# Frozen_Slimes_v2_BMI.net
KiCad netlist of a schematic drawn in EasyEDA
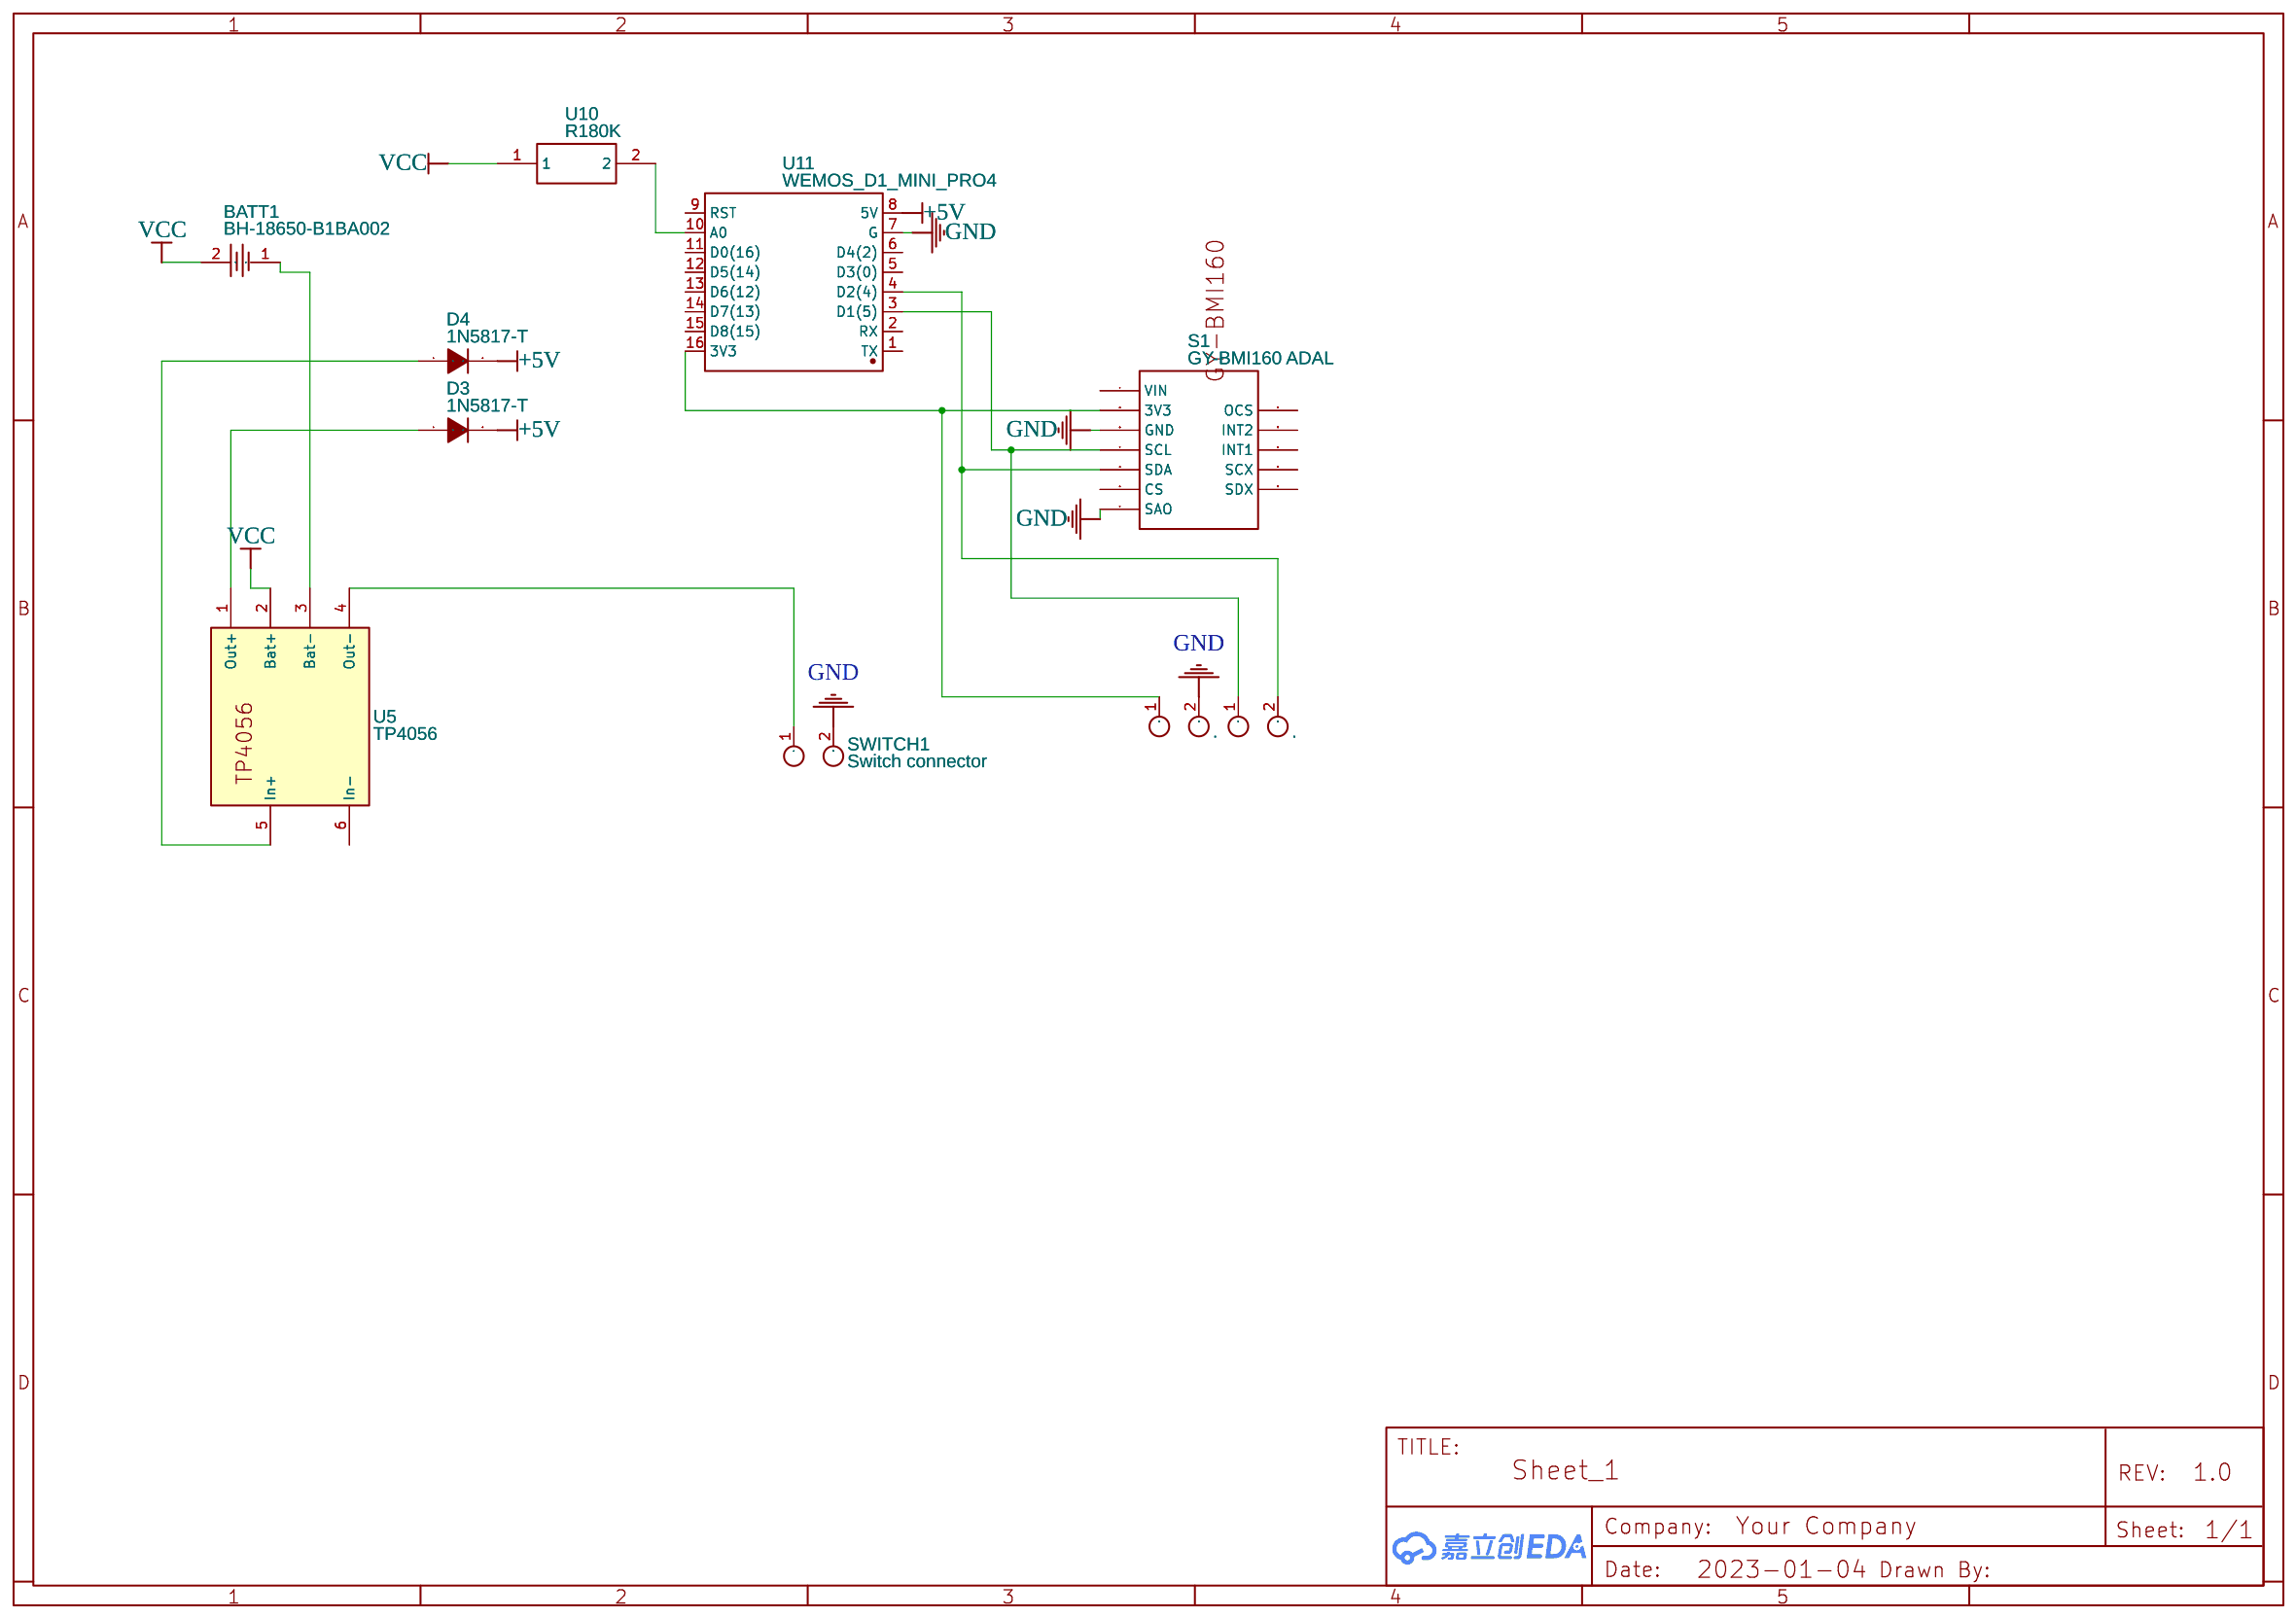
[diagram p0: schematic sheet]

(export (version "E")
  (design (tool "Eeschema 10.0.6"))
  (components
    (comp (ref "BATT1")
      (value "BH-18650-B1BA002")
      (fields (field (name "BOM_Supplier Part") "C2988620"))
      (libsource (lib "") (part "BH-18650-B1BA002"))
    )
    (comp (ref "D3")
      (value "1N5817-T")
      (fields (field (name "BOM_Supplier Part") "C507852"))
      (libsource (lib "") (part "1N5817-T"))
    )
    (comp (ref "D4")
      (value "1N5817-T")
      (fields (field (name "BOM_Supplier Part") "C507852"))
      (libsource (lib "") (part "1N5817-T"))
    )
    (comp (ref "S1") (value "GY-BMI160 ADAL") (libsource (lib "") (part "GY-BMI160 ADAL")))
    (comp (ref "SWITCH1") (value "Switch connector") (libsource (lib "") (part "2XSOLDER PAD")))
    (comp (ref "U5") (value "TP4056") (libsource (lib "") (part "TP4056")))
    (comp (ref "U8") (value ".") (libsource (lib "") (part "2XSOLDER PAD_1")))
    (comp (ref "U9") (value ".") (libsource (lib "") (part "2XSOLDER PAD_1")))
    (comp (ref "U10") (value "R180K") (libsource (lib "") (part "R180K")))
    (comp (ref "U11")
      (value "WEMOS_D1_MINI_PRO4")
      (fields
        (field (name "BOM_Manufacturer Part") "Wemos_D1_mini_Pro4")
        (field (name "BOM_Supplier Part") "C2837266")
      )
      (libsource (lib "") (part "WEMOS_D1_MINI_PRO4"))
    )
  )
  (nets
    (net (code "1") (name "+5V") (class "Default")
      (node (ref "D3") (pin "2") (pinfunction "K_2") (pintype "unspecified"))
      (node (ref "D4") (pin "2") (pinfunction "K_2") (pintype "unspecified"))
      (node (ref "U11") (pin "8") (pinfunction "5V_8") (pintype "unspecified"))
    )
    (net (code "2") (name "GND") (class "Default")
      (node (ref "S1") (pin "1") (pinfunction "SAO_1") (pintype "unspecified"))
      (node (ref "S1") (pin "5") (pinfunction "GND_5") (pintype "unspecified"))
      (node (ref "SWITCH1") (pin "2") (pinfunction "2_2") (pintype "unspecified"))
      (node (ref "U11") (pin "7") (pinfunction "G_7") (pintype "unspecified"))
      (node (ref "U9") (pin "2") (pinfunction "2_2") (pintype "unspecified"))
    )
    (net (code "3") (name "Net-(D3-A)") (class "Default")
      (node (ref "D3") (pin "1") (pinfunction "A_1") (pintype "unspecified"))
      (node (ref "U5") (pin "1") (pinfunction "Out+_1") (pintype "unspecified"))
    )
    (net (code "4") (name "Net-(D4-A)") (class "Default")
      (node (ref "D4") (pin "1") (pinfunction "A_1") (pintype "unspecified"))
      (node (ref "U5") (pin "5") (pinfunction "In+_5") (pintype "unspecified"))
    )
    (net (code "5") (name "Net-(S1-3V3)") (class "Default")
      (node (ref "S1") (pin "6") (pinfunction "3V3_6") (pintype "unspecified"))
      (node (ref "U11") (pin "16") (pinfunction "3V3_16") (pintype "unspecified"))
      (node (ref "U9") (pin "1") (pinfunction "1_1") (pintype "unspecified"))
    )
    (net (code "6") (name "Net-(S1-SCL)") (class "Default")
      (node (ref "S1") (pin "4") (pinfunction "SCL_4") (pintype "unspecified"))
      (node (ref "U11") (pin "3") (pinfunction "D1(5)_3") (pintype "unspecified"))
      (node (ref "U8") (pin "1") (pinfunction "1_1") (pintype "unspecified"))
    )
    (net (code "7") (name "Net-(S1-SDA)") (class "Default")
      (node (ref "S1") (pin "3") (pinfunction "SDA_3") (pintype "unspecified"))
      (node (ref "U11") (pin "4") (pinfunction "D2(4)_4") (pintype "unspecified"))
      (node (ref "U8") (pin "2") (pinfunction "2_2") (pintype "unspecified"))
    )
    (net (code "8") (name "Net-(U5-Bat-)") (class "Default")
      (node (ref "BATT1") (pin "1") (pinfunction "1_1") (pintype "input"))
      (node (ref "U5") (pin "3") (pinfunction "Bat-_3") (pintype "unspecified"))
    )
    (net (code "9") (name "Net-(U5-Out-)") (class "Default")
      (node (ref "SWITCH1") (pin "1") (pinfunction "1_1") (pintype "unspecified"))
      (node (ref "U5") (pin "4") (pinfunction "Out-_4") (pintype "unspecified"))
    )
    (net (code "10") (name "Net-(U11-A0)") (class "Default")
      (node (ref "U10") (pin "2") (pinfunction "2_2") (pintype "unspecified"))
      (node (ref "U11") (pin "10") (pinfunction "A0_10") (pintype "unspecified"))
    )
    (net (code "11") (name "VCC") (class "Default")
      (node (ref "BATT1") (pin "2") (pinfunction "2_2") (pintype "input"))
      (node (ref "U10") (pin "1") (pinfunction "1_1") (pintype "unspecified"))
      (node (ref "U5") (pin "2") (pinfunction "Bat+_2") (pintype "unspecified"))
    )
    (net (code "12") (name "unconnected-(S1-CS-Pad2)") (class "Default")
      (node (ref "S1") (pin "2") (pinfunction "CS_2") (pintype "unspecified"))
    )
    (net (code "13") (name "unconnected-(S1-INT1-Pad10)") (class "Default")
      (node (ref "S1") (pin "10") (pinfunction "INT1_10") (pintype "unspecified"))
    )
    (net (code "14") (name "unconnected-(S1-INT2-Pad9)") (class "Default")
      (node (ref "S1") (pin "9") (pinfunction "INT2_9") (pintype "unspecified"))
    )
    (net (code "15") (name "unconnected-(S1-OCS-Pad8)") (class "Default")
      (node (ref "S1") (pin "8") (pinfunction "OCS_8") (pintype "unspecified"))
    )
    (net (code "16") (name "unconnected-(S1-SCX-Pad11)") (class "Default")
      (node (ref "S1") (pin "11") (pinfunction "SCX_11") (pintype "unspecified"))
    )
    (net (code "17") (name "unconnected-(S1-SDX-Pad12)") (class "Default")
      (node (ref "S1") (pin "12") (pinfunction "SDX_12") (pintype "unspecified"))
    )
    (net (code "18") (name "unconnected-(S1-VIN-Pad7)") (class "Default")
      (node (ref "S1") (pin "7") (pinfunction "VIN_7") (pintype "unspecified"))
    )
    (net (code "19") (name "unconnected-(U5-In--Pad6)") (class "Default")
      (node (ref "U5") (pin "6") (pinfunction "In-_6") (pintype "unspecified"))
    )
    (net (code "20") (name "unconnected-(U11-D0(16)-Pad11)") (class "Default")
      (node (ref "U11") (pin "11") (pinfunction "D0(16)_11") (pintype "unspecified"))
    )
    (net (code "21") (name "unconnected-(U11-D3(0)-Pad5)") (class "Default")
      (node (ref "U11") (pin "5") (pinfunction "D3(0)_5") (pintype "unspecified"))
    )
    (net (code "22") (name "unconnected-(U11-D4(2)-Pad6)") (class "Default")
      (node (ref "U11") (pin "6") (pinfunction "D4(2)_6") (pintype "unspecified"))
    )
    (net (code "23") (name "unconnected-(U11-D5(14)-Pad12)") (class "Default")
      (node (ref "U11") (pin "12") (pinfunction "D5(14)_12") (pintype "unspecified"))
    )
    (net (code "24") (name "unconnected-(U11-D6(12)-Pad13)") (class "Default")
      (node (ref "U11") (pin "13") (pinfunction "D6(12)_13") (pintype "unspecified"))
    )
    (net (code "25") (name "unconnected-(U11-D7(13)-Pad14)") (class "Default")
      (node (ref "U11") (pin "14") (pinfunction "D7(13)_14") (pintype "unspecified"))
    )
    (net (code "26") (name "unconnected-(U11-D8(15)-Pad15)") (class "Default")
      (node (ref "U11") (pin "15") (pinfunction "D8(15)_15") (pintype "unspecified"))
    )
    (net (code "27") (name "unconnected-(U11-RST-Pad9)") (class "Default")
      (node (ref "U11") (pin "9") (pinfunction "RST_9") (pintype "unspecified"))
    )
    (net (code "28") (name "unconnected-(U11-RX-Pad2)") (class "Default")
      (node (ref "U11") (pin "2") (pinfunction "RX_2") (pintype "unspecified"))
    )
    (net (code "29") (name "unconnected-(U11-TX-Pad1)") (class "Default")
      (node (ref "U11") (pin "1") (pinfunction "TX_1") (pintype "unspecified"))
    )
  )
)
